# Schematics.net
KiCad netlist of a schematic drawn in EasyEDA
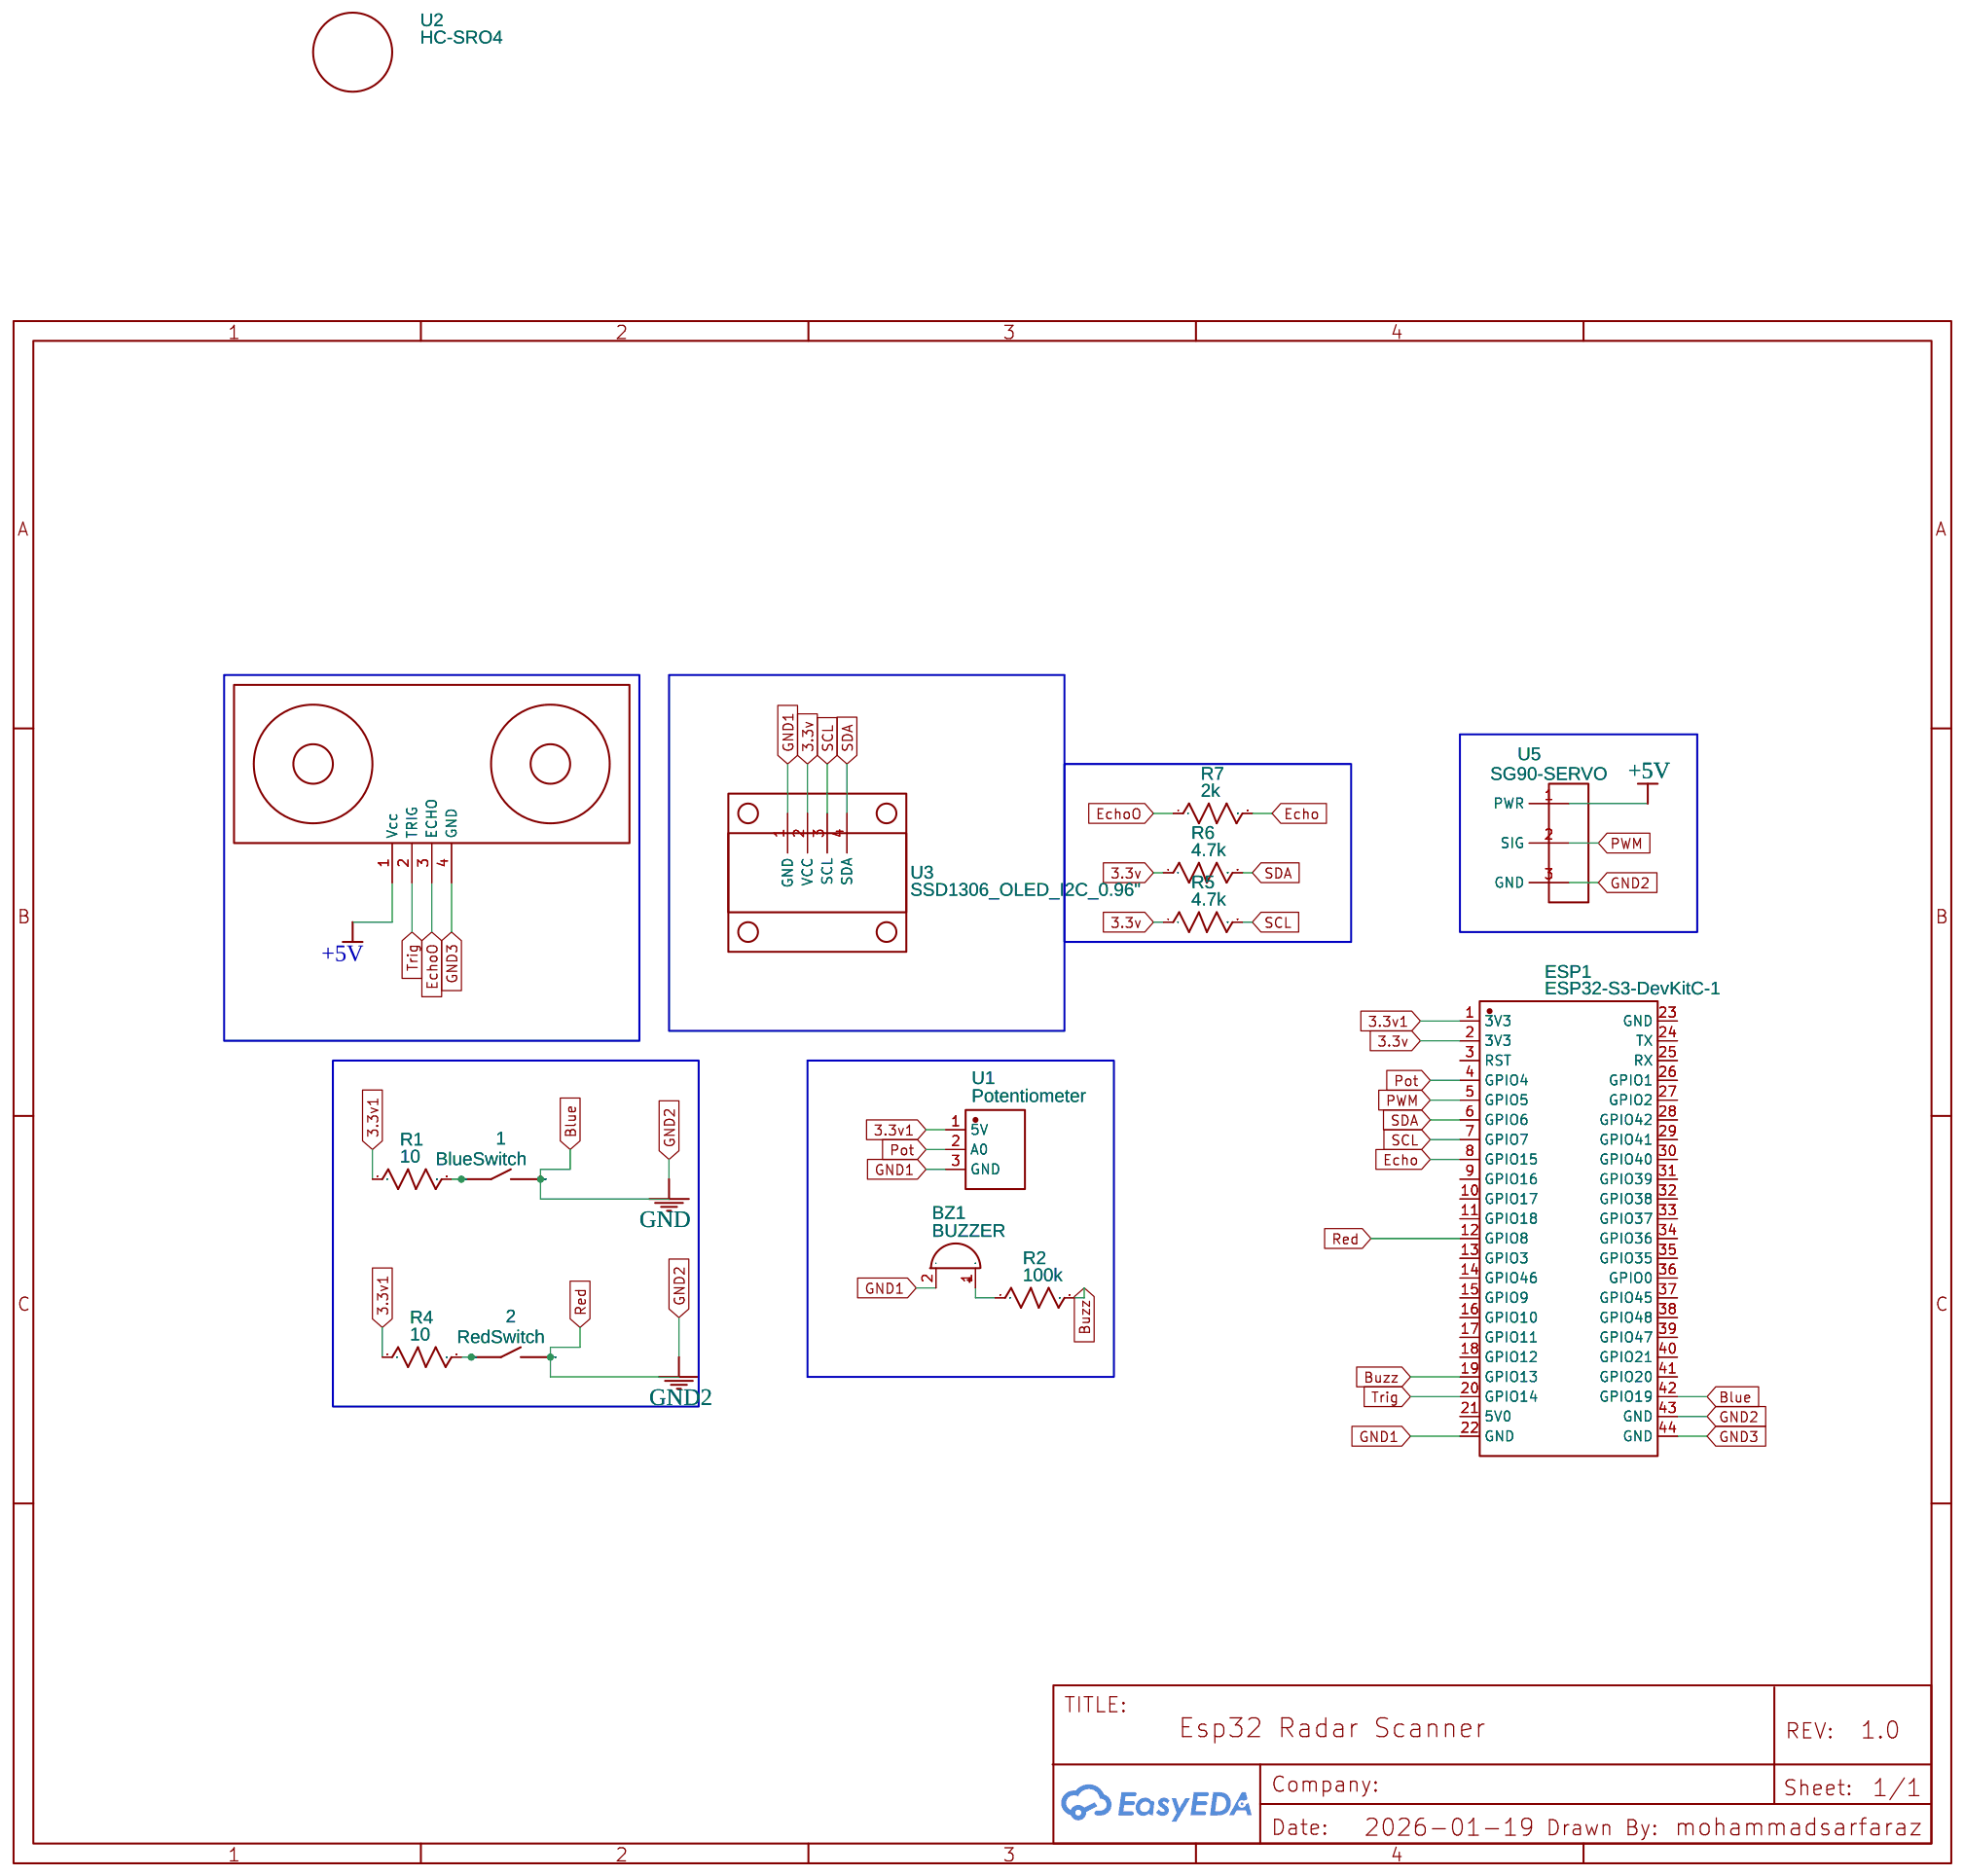
[diagram p0: schematic sheet]

(export (version "E")
  (design (tool "Eeschema 10.0.6"))
  (components
    (comp (ref "1") (value "BlueSwitch") (libsource (lib "") (part "4.5X4.5-SMD-TACTILE-SWITCH")))
    (comp (ref "2") (value "RedSwitch") (libsource (lib "") (part "4.5X4.5-SMD-TACTILE-SWITCH")))
    (comp (ref "BZ1") (value "BUZZER") (libsource (lib "") (part "BUZZER 12X9.5 FATHBOARD")))
    (comp (ref "ESP1") (value "ESP32-S3-DevKitC-1") (libsource (lib "") (part "ESP32-S3-DevKitC-1")))
    (comp (ref "R1") (value "10") (libsource (lib "") (part "R_0603_US")))
    (comp (ref "R2") (value "100k") (libsource (lib "") (part "R_0603_US")))
    (comp (ref "R4") (value "10") (libsource (lib "") (part "R_0603_US")))
    (comp (ref "R5") (value "4.7k") (libsource (lib "") (part "R_0603_US")))
    (comp (ref "R6") (value "4.7k") (libsource (lib "") (part "R_0603_US")))
    (comp (ref "R7") (value "2k") (libsource (lib "") (part "R_0603_US")))
    (comp (ref "U1") (value "Potentiometer") (libsource (lib "") (part "Potentiometer")))
    (comp (ref "U2") (value "HC-SRO4") (libsource (lib "") (part "HC-SRO4")))
    (comp (ref "U3")
      (value "SSD1306_OLED_I2C_0.96\"")
      (libsource (lib "") (part "SSD1306_OLED_I2C_0.96{dblquote}"))
    )
    (comp (ref "U5") (value "SG90-SERVO") (libsource (lib "") (part "SG90-SERVO")))
  )
  (nets
    (net (code "1") (name "+5V") (class "Default")
      (node (ref "U2") (pin "1") (pinfunction "Vcc_1") (pintype "unspecified"))
      (node (ref "U5") (pin "1") (pinfunction "PWR_1") (pintype "unspecified"))
    )
    (net (code "2") (name "3.3v") (class "Default")
      (node (ref "ESP1") (pin "2") (pinfunction "3V3_2") (pintype "unspecified"))
      (node (ref "R5") (pin "1") (pinfunction "1_1") (pintype "unspecified"))
      (node (ref "R6") (pin "1") (pinfunction "1_1") (pintype "unspecified"))
      (node (ref "U3") (pin "2") (pinfunction "VCC_2") (pintype "unspecified"))
    )
    (net (code "3") (name "3.3v1") (class "Default")
      (node (ref "ESP1") (pin "1") (pinfunction "3V3_1") (pintype "unspecified"))
      (node (ref "R1") (pin "1") (pinfunction "1_1") (pintype "unspecified"))
      (node (ref "R4") (pin "1") (pinfunction "1_1") (pintype "unspecified"))
      (node (ref "U1") (pin "1") (pinfunction "5V_1") (pintype "unspecified"))
    )
    (net (code "4") (name "Blue") (class "Default")
      (node (ref "1") (pin "2.1") (pinfunction "S2_2.1") (pintype "bidirectional"))
      (node (ref "1") (pin "2.2") (pinfunction "S2_2.2") (pintype "bidirectional"))
      (node (ref "ESP1") (pin "42") (pinfunction "GPIO19_42") (pintype "unspecified"))
    )
    (net (code "5") (name "Buzz") (class "Default")
      (node (ref "ESP1") (pin "19") (pinfunction "GPIO13_19") (pintype "unspecified"))
      (node (ref "R2") (pin "2") (pinfunction "2_2") (pintype "unspecified"))
    )
    (net (code "6") (name "Echo") (class "Default")
      (node (ref "ESP1") (pin "8") (pinfunction "GPIO15_8") (pintype "unspecified"))
      (node (ref "R7") (pin "2") (pinfunction "2_2") (pintype "unspecified"))
    )
    (net (code "7") (name "EchoO") (class "Default")
      (node (ref "R7") (pin "1") (pinfunction "1_1") (pintype "unspecified"))
      (node (ref "U2") (pin "3") (pinfunction "ECHO_3") (pintype "unspecified"))
    )
    (net (code "8") (name "GND1") (class "Default")
      (node (ref "BZ1") (pin "2") (pinfunction "-_2") (pintype "unspecified"))
      (node (ref "ESP1") (pin "22") (pinfunction "GND_22") (pintype "unspecified"))
      (node (ref "U1") (pin "3") (pinfunction "GND_3") (pintype "unspecified"))
      (node (ref "U3") (pin "1") (pinfunction "GND_1") (pintype "unspecified"))
    )
    (net (code "9") (name "GND2") (class "Default")
      (node (ref "ESP1") (pin "43") (pinfunction "GND_43") (pintype "unspecified"))
      (node (ref "U5") (pin "3") (pinfunction "GND_3") (pintype "unspecified"))
    )
    (net (code "10") (name "GND3") (class "Default")
      (node (ref "ESP1") (pin "44") (pinfunction "GND_44") (pintype "unspecified"))
      (node (ref "U2") (pin "4") (pinfunction "GND_4") (pintype "unspecified"))
    )
    (net (code "11") (name "Net-(1-S1-Pad1.1)") (class "Default")
      (node (ref "1") (pin "1.1") (pinfunction "S1_1.1") (pintype "bidirectional"))
      (node (ref "1") (pin "1.2") (pinfunction "S1_1.2") (pintype "bidirectional"))
      (node (ref "R1") (pin "2") (pinfunction "2_2") (pintype "unspecified"))
    )
    (net (code "12") (name "Net-(2-S1-Pad1.1)") (class "Default")
      (node (ref "2") (pin "1.1") (pinfunction "S1_1.1") (pintype "bidirectional"))
      (node (ref "2") (pin "1.2") (pinfunction "S1_1.2") (pintype "bidirectional"))
      (node (ref "R4") (pin "2") (pinfunction "2_2") (pintype "unspecified"))
    )
    (net (code "13") (name "Net-(BZ1-+)") (class "Default")
      (node (ref "BZ1") (pin "1") (pinfunction "+_1") (pintype "unspecified"))
      (node (ref "R2") (pin "1") (pinfunction "1_1") (pintype "unspecified"))
    )
    (net (code "14") (name "PWM") (class "Default")
      (node (ref "ESP1") (pin "5") (pinfunction "GPIO5_5") (pintype "unspecified"))
      (node (ref "U5") (pin "2") (pinfunction "SIG_2") (pintype "unspecified"))
    )
    (net (code "15") (name "Pot") (class "Default")
      (node (ref "ESP1") (pin "4") (pinfunction "GPIO4_4") (pintype "unspecified"))
      (node (ref "U1") (pin "2") (pinfunction "A0_2") (pintype "unspecified"))
    )
    (net (code "16") (name "Red") (class "Default")
      (node (ref "2") (pin "2.1") (pinfunction "S2_2.1") (pintype "bidirectional"))
      (node (ref "2") (pin "2.2") (pinfunction "S2_2.2") (pintype "bidirectional"))
      (node (ref "ESP1") (pin "12") (pinfunction "GPIO8_12") (pintype "unspecified"))
    )
    (net (code "17") (name "SCL") (class "Default")
      (node (ref "ESP1") (pin "7") (pinfunction "GPIO7_7") (pintype "unspecified"))
      (node (ref "R5") (pin "2") (pinfunction "2_2") (pintype "unspecified"))
      (node (ref "U3") (pin "3") (pinfunction "SCL_3") (pintype "unspecified"))
    )
    (net (code "18") (name "SDA") (class "Default")
      (node (ref "ESP1") (pin "6") (pinfunction "GPIO6_6") (pintype "unspecified"))
      (node (ref "R6") (pin "2") (pinfunction "2_2") (pintype "unspecified"))
      (node (ref "U3") (pin "4") (pinfunction "SDA_4") (pintype "unspecified"))
    )
    (net (code "19") (name "Trig") (class "Default")
      (node (ref "ESP1") (pin "20") (pinfunction "GPIO14_20") (pintype "unspecified"))
      (node (ref "U2") (pin "2") (pinfunction "TRIG_2") (pintype "unspecified"))
    )
    (net (code "20") (name "unconnected-(ESP1-5V0-Pad21)") (class "Default")
      (node (ref "ESP1") (pin "21") (pinfunction "5V0_21") (pintype "unspecified"))
    )
    (net (code "21") (name "unconnected-(ESP1-GND-Pad23)") (class "Default")
      (node (ref "ESP1") (pin "23") (pinfunction "GND_23") (pintype "unspecified"))
    )
    (net (code "22") (name "unconnected-(ESP1-GPIO0-Pad36)") (class "Default")
      (node (ref "ESP1") (pin "36") (pinfunction "GPIO0_36") (pintype "unspecified"))
    )
    (net (code "23") (name "unconnected-(ESP1-GPIO1-Pad26)") (class "Default")
      (node (ref "ESP1") (pin "26") (pinfunction "GPIO1_26") (pintype "unspecified"))
    )
    (net (code "24") (name "unconnected-(ESP1-GPIO2-Pad27)") (class "Default")
      (node (ref "ESP1") (pin "27") (pinfunction "GPIO2_27") (pintype "unspecified"))
    )
    (net (code "25") (name "unconnected-(ESP1-GPIO3-Pad13)") (class "Default")
      (node (ref "ESP1") (pin "13") (pinfunction "GPIO3_13") (pintype "unspecified"))
    )
    (net (code "26") (name "unconnected-(ESP1-GPIO9-Pad15)") (class "Default")
      (node (ref "ESP1") (pin "15") (pinfunction "GPIO9_15") (pintype "unspecified"))
    )
    (net (code "27") (name "unconnected-(ESP1-GPIO10-Pad16)") (class "Default")
      (node (ref "ESP1") (pin "16") (pinfunction "GPIO10_16") (pintype "unspecified"))
    )
    (net (code "28") (name "unconnected-(ESP1-GPIO11-Pad17)") (class "Default")
      (node (ref "ESP1") (pin "17") (pinfunction "GPIO11_17") (pintype "unspecified"))
    )
    (net (code "29") (name "unconnected-(ESP1-GPIO12-Pad18)") (class "Default")
      (node (ref "ESP1") (pin "18") (pinfunction "GPIO12_18") (pintype "unspecified"))
    )
    (net (code "30") (name "unconnected-(ESP1-GPIO16-Pad9)") (class "Default")
      (node (ref "ESP1") (pin "9") (pinfunction "GPIO16_9") (pintype "unspecified"))
    )
    (net (code "31") (name "unconnected-(ESP1-GPIO17-Pad10)") (class "Default")
      (node (ref "ESP1") (pin "10") (pinfunction "GPIO17_10") (pintype "unspecified"))
    )
    (net (code "32") (name "unconnected-(ESP1-GPIO18-Pad11)") (class "Default")
      (node (ref "ESP1") (pin "11") (pinfunction "GPIO18_11") (pintype "unspecified"))
    )
    (net (code "33") (name "unconnected-(ESP1-GPIO20-Pad41)") (class "Default")
      (node (ref "ESP1") (pin "41") (pinfunction "GPIO20_41") (pintype "unspecified"))
    )
    (net (code "34") (name "unconnected-(ESP1-GPIO21-Pad40)") (class "Default")
      (node (ref "ESP1") (pin "40") (pinfunction "GPIO21_40") (pintype "unspecified"))
    )
    (net (code "35") (name "unconnected-(ESP1-GPIO35-Pad35)") (class "Default")
      (node (ref "ESP1") (pin "35") (pinfunction "GPIO35_35") (pintype "unspecified"))
    )
    (net (code "36") (name "unconnected-(ESP1-GPIO36-Pad34)") (class "Default")
      (node (ref "ESP1") (pin "34") (pinfunction "GPIO36_34") (pintype "unspecified"))
    )
    (net (code "37") (name "unconnected-(ESP1-GPIO37-Pad33)") (class "Default")
      (node (ref "ESP1") (pin "33") (pinfunction "GPIO37_33") (pintype "unspecified"))
    )
    (net (code "38") (name "unconnected-(ESP1-GPIO38-Pad32)") (class "Default")
      (node (ref "ESP1") (pin "32") (pinfunction "GPIO38_32") (pintype "unspecified"))
    )
    (net (code "39") (name "unconnected-(ESP1-GPIO39-Pad31)") (class "Default")
      (node (ref "ESP1") (pin "31") (pinfunction "GPIO39_31") (pintype "unspecified"))
    )
    (net (code "40") (name "unconnected-(ESP1-GPIO40-Pad30)") (class "Default")
      (node (ref "ESP1") (pin "30") (pinfunction "GPIO40_30") (pintype "unspecified"))
    )
    (net (code "41") (name "unconnected-(ESP1-GPIO41-Pad29)") (class "Default")
      (node (ref "ESP1") (pin "29") (pinfunction "GPIO41_29") (pintype "unspecified"))
    )
    (net (code "42") (name "unconnected-(ESP1-GPIO42-Pad28)") (class "Default")
      (node (ref "ESP1") (pin "28") (pinfunction "GPIO42_28") (pintype "unspecified"))
    )
    (net (code "43") (name "unconnected-(ESP1-GPIO45-Pad37)") (class "Default")
      (node (ref "ESP1") (pin "37") (pinfunction "GPIO45_37") (pintype "unspecified"))
    )
    (net (code "44") (name "unconnected-(ESP1-GPIO46-Pad14)") (class "Default")
      (node (ref "ESP1") (pin "14") (pinfunction "GPIO46_14") (pintype "unspecified"))
    )
    (net (code "45") (name "unconnected-(ESP1-GPIO47-Pad39)") (class "Default")
      (node (ref "ESP1") (pin "39") (pinfunction "GPIO47_39") (pintype "unspecified"))
    )
    (net (code "46") (name "unconnected-(ESP1-GPIO48-Pad38)") (class "Default")
      (node (ref "ESP1") (pin "38") (pinfunction "GPIO48_38") (pintype "unspecified"))
    )
    (net (code "47") (name "unconnected-(ESP1-RST-Pad3)") (class "Default")
      (node (ref "ESP1") (pin "3") (pinfunction "RST_3") (pintype "unspecified"))
    )
    (net (code "48") (name "unconnected-(ESP1-RX-Pad25)") (class "Default")
      (node (ref "ESP1") (pin "25") (pinfunction "RX_25") (pintype "unspecified"))
    )
    (net (code "49") (name "unconnected-(ESP1-TX-Pad24)") (class "Default")
      (node (ref "ESP1") (pin "24") (pinfunction "TX_24") (pintype "unspecified"))
    )
  )
)
